# EVB_Gatedriver.net
KiCad netlist of a schematic drawn in Altium Designer
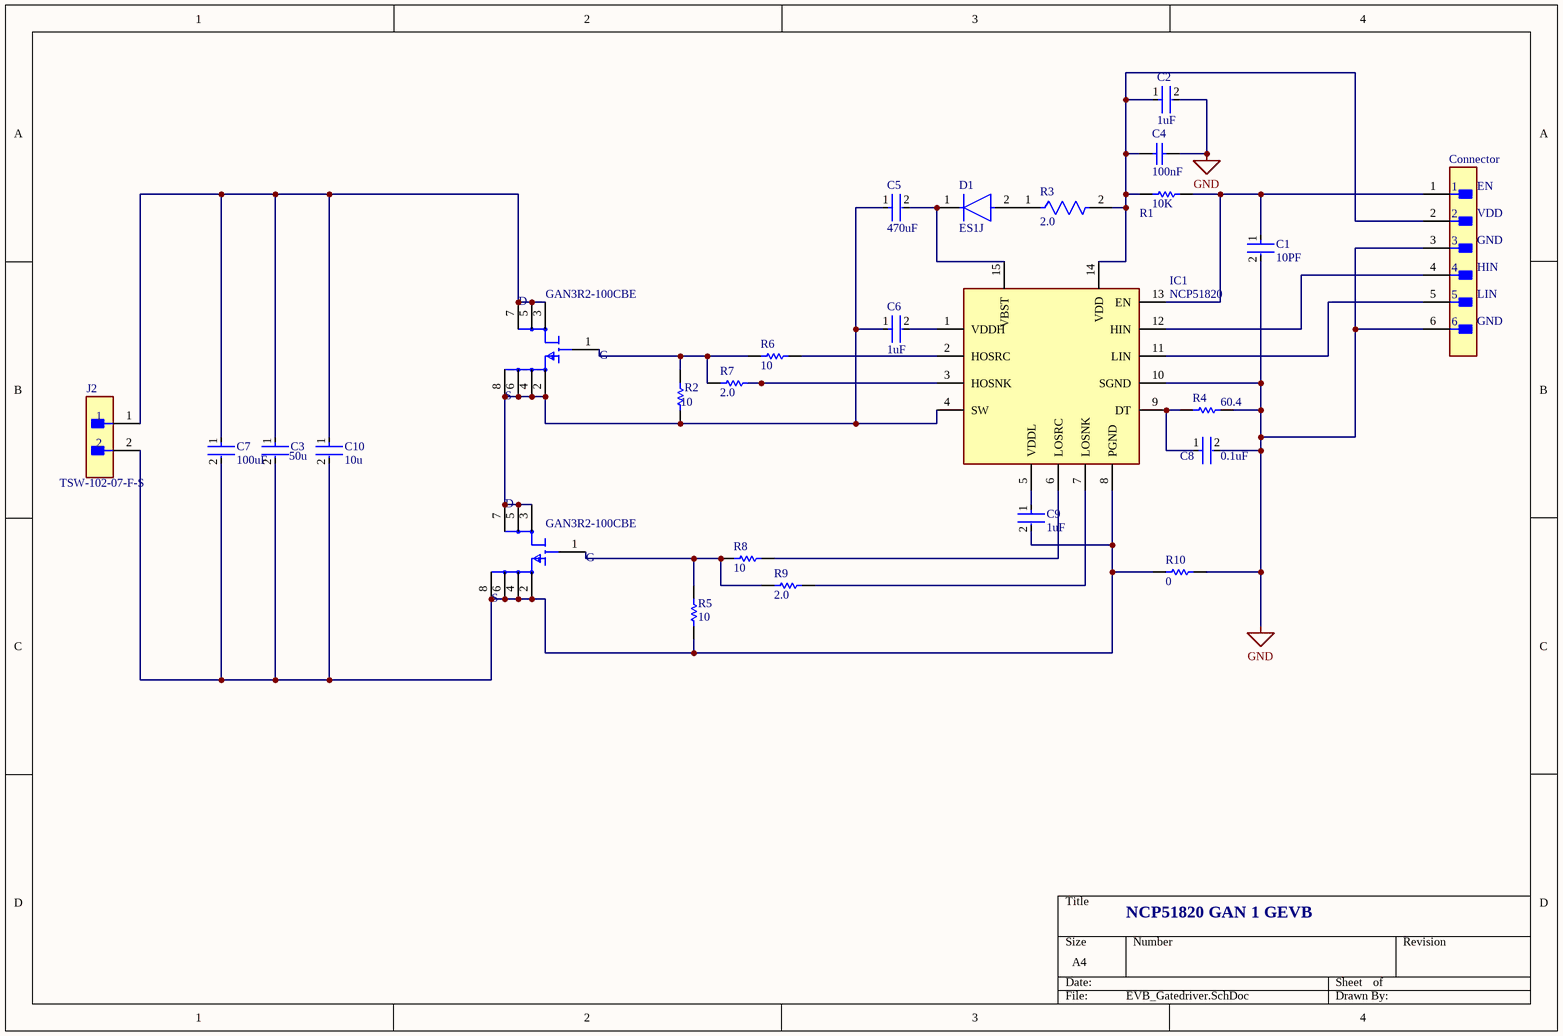
[diagram p0: EVB_Gatedriver.SchDoc]

(export (version "E")
  (design (tool "Eeschema 10.0.6"))
  (components
    (comp (ref "1")
      (value "GAN3R2-100CBE")
      (footprint "FP-WLCSP8-SOT8072-MFG")
      (libsource (lib "Alpha_library") (part "GAN3R2-100CBE_1"))
    )
    (comp (ref "2")
      (value "GAN3R2-100CBE")
      (footprint "FP-WLCSP8-SOT8072-MFG")
      (libsource (lib "Alpha_library") (part "GAN3R2-100CBE_1"))
    )
    (comp (ref "C1")
      (value "10PF")
      (footprint "FP-C1206C-EB-MFG")
      (description "CAP CER 10PF 50V C0G/NP0 1206")
      (fields
        (field (name "OCTOPART") "https://octopart.com/c1206c100j5gactu-kemet-87062")
        (field (name "MANUFACTURER PART NUMBER") "C1206C100J5GACTU")
      )
      (libsource (lib "Altium Content Vault") (part "b4654b650e69147ec39a6b967a45e02"))
    )
    (comp (ref "C2")
      (value "1uF")
      (footprint "FP-CC0805-0_85-MFG")
      (description "CC0805 1 uF X7R 10.00% 16 V")
      (fields (field (name "MANUFACTURER") "Yageo"))
      (libsource (lib "Altium Content Vault") (part "11868f565c42a9108669ba33697ecf6"))
    )
    (comp (ref "C3")
      (value "50u")
      (footprint "FP-CGA5L-0_3-0_1-IPC_B")
      (description "Cap Ceramic 100nF 450V X7T 10% Pad SMD 1206 +125°C Automotive T/R")
      (fields (field (name "TOLERANCE") "10%"))
      (libsource (lib "Altium Content Vault") (part "b4654b650e69147ec39a6b967a45e02"))
    )
    (comp (ref "C4")
      (value "100nF")
      (footprint "CAPC2013X145X48LL20T23")
      (fields (field (name "MANUFACTURER") "Vitramon") (field (name "PART NUMBER") "VJ0805Y104JXXAT"))
      (libsource (lib "Altium Content Vault") (part "CAP"))
    )
    (comp (ref "C5")
      (value "470uF")
      (footprint "FP-C1206C-EB-MFG")
      (description "CAP CER 0.47UF 25V X5R 1206")
      (fields
        (field (name "MANUFACTURER") "KEMET")
        (field (name "OCTOPART") "https://octopart.com/c1206c474k3pactu-kemet-16430430")
      )
      (libsource (lib "Altium Content Vault") (part "b4654b650e69147ec39a6b967a45e02"))
    )
    (comp (ref "C6")
      (value "1uF")
      (footprint "FP-1206-L_3_2_0_15-W_1_6-IPC_A")
      (description "None")
      (fields (field (name "TOLERANCE") "10%") (field (name "VOLTAGE") "25V"))
      (libsource (lib "Altium Content Vault") (part "02cd4be3c70576c341d710602a673aa"))
    )
    (comp (ref "C7")
      (value "100uF")
      (footprint "FP-CGA5L-0_3-0_1-IPC_B")
      (description "Cap Ceramic 100nF 450V X7T 10% Pad SMD 1206 +125°C Automotive T/R")
      (fields (field (name "TOLERANCE") "10%"))
      (libsource (lib "Altium Content Vault") (part "b4654b650e69147ec39a6b967a45e02"))
    )
    (comp (ref "C8")
      (value "0.1uF")
      (footprint "FP-C1206C-EB-MFG")
      (description "CAP CER 0.1UF 25V 10% X7R 1206")
      (fields
        (field (name "MANUFACTURER") "KEMET")
        (field (name "OCTOPART") "https://octopart.com/c1206c104k3ractu-kemet-9144317")
      )
      (libsource (lib "Altium Content Vault") (part "b4654b650e69147ec39a6b967a45e02"))
    )
    (comp (ref "C9")
      (value "1uF")
      (footprint "FP-1206-L_3_2_0_15-W_1_6-IPC_A")
      (description "None")
      (fields (field (name "TOLERANCE") "10%") (field (name "VOLTAGE") "25V"))
      (libsource (lib "Altium Content Vault") (part "02cd4be3c70576c341d710602a673aa"))
    )
    (comp (ref "C10")
      (value "10u")
      (footprint "FP-CGA5L-0_3-0_1-IPC_B")
      (description "Cap Ceramic 100nF 450V X7T 10% Pad SMD 1206 +125°C Automotive T/R")
      (fields (field (name "TOLERANCE") "10%"))
      (libsource (lib "Altium Content Vault") (part "b4654b650e69147ec39a6b967a45e02"))
    )
    (comp (ref "Connector")
      (value "~")
      (footprint "FP-22-28-4060-MFG")
      (description "CONN HEADER VERT 6POS 2.54MM")
      (fields (field (name "MPN") "22-28-4060"))
      (libsource (lib "Altium Content Vault") (part "f2cb566baf1c37ab5a3b8e90bbeafd6"))
    )
    (comp (ref "D1")
      (value "ES1J")
      (footprint "FP-403AE-MFG")
      (description "DIODE GEN PURP 400V 1A SMA")
      (fields
        (field (name "OCTOPART") "https://octopart.com/es1g-on+semiconductor-84324858")
        (field (name "MANUFACTURER") "ON Semiconductor")
      )
      (libsource (lib "Altium Content Vault") (part "d7152d700b627762746794eb795d46e"))
    )
    (comp (ref "IC1")
      (value "NCP51820")
      (footprint "NCP51820")
      (description "Integrated Circuit")
      (libsource (lib "Alpha_library") (part "NCP51820"))
    )
    (comp (ref "J2")
      (value "TSW-102-07-F-S")
      (footprint "FP-TSW-102-07-F-S-MFG")
      (description "CONN HEADER VERT 2POS 2.54MM")
      (libsource (lib "Altium Content Vault") (part "3bc925449376181038e59eaffc5286c"))
    )
    (comp (ref "R1")
      (value "10K")
      (footprint "RESC2013X60X35NL10T20")
      (description "Chip Resistor, 10 KOhm, +/- 1%, 0.125 W, -55 to 155 degC, 0805 (2012 Metric), RoHS, Tape and Reel")
      (fields (field (name "MANUFACTURER") "Yageo"))
      (libsource (lib "Altium Content Vault") (part "RES-2"))
    )
    (comp (ref "R2")
      (value "10")
      (footprint "RESC2013X60X35NL10T20")
      (description "Chip Resistor, 10 KOhm, +/- 1%, 0.125 W, -55 to 155 degC, 0805 (2012 Metric), RoHS, Tape and Reel")
      (fields (field (name "MANUFACTURER") "Yageo"))
      (libsource (lib "Altium Content Vault") (part "RES-2"))
    )
    (comp (ref "R3")
      (value "2.0")
      (footprint "FP-RMCF1206-IPC_C")
      (description "RES 2 OHM 1% 1/4W 1206")
      (fields (field (name "TOLERANCE") "1%"))
      (libsource (lib "Altium Content Vault") (part "1029c3af85768c4190bb7ad29bc67b5"))
    )
    (comp (ref "R4")
      (value "60.4")
      (footprint "RESC3116X65X40LL10T20")
      (fields (field (name "PART NUMBER") "RC1206FR-1360R4L") (field (name "MANUFACTURER") "Yageo"))
      (libsource (lib "Altium Content Vault") (part "RES"))
    )
    (comp (ref "R5")
      (value "10")
      (footprint "RESC2013X60X35NL10T20")
      (description "Chip Resistor, 10 KOhm, +/- 1%, 0.125 W, -55 to 155 degC, 0805 (2012 Metric), RoHS, Tape and Reel")
      (fields (field (name "MANUFACTURER") "Yageo"))
      (libsource (lib "Altium Content Vault") (part "RES-2"))
    )
    (comp (ref "R6")
      (value "10")
      (footprint "RESC2013X60X35ML10T20")
      (description "Chip Resistor, 10 Ohm, +/- 1%, 0.125 W, -55 to 155 degC, 0805 (2012 Metric), RoHS, Tape and Reel")
      (fields (field (name "MANUFACTURER") "Yageo") (field (name "TOLERANCE") "1%"))
      (libsource (lib "Altium Content Vault") (part "RES-2"))
    )
    (comp (ref "R7")
      (value "2.0")
      (footprint "RESC0201(0603)_M")
      (description "2R 0.05W 5% 0201 (0603 Metric)  SMD")
      (fields (field (name "POWER") "0.05 W") (field (name "TOLERANCE") "5 %"))
      (libsource (lib "Altium Content Vault") (part "RES"))
    )
    (comp (ref "R8")
      (value "10")
      (footprint "RESC2013X60X35ML10T20")
      (description "Chip Resistor, 10 Ohm, +/- 1%, 0.125 W, -55 to 155 degC, 0805 (2012 Metric), RoHS, Tape and Reel")
      (fields (field (name "MANUFACTURER") "Yageo") (field (name "TOLERANCE") "1%"))
      (libsource (lib "Altium Content Vault") (part "RES-2"))
    )
    (comp (ref "R9")
      (value "2.0")
      (footprint "RESC0201(0603)_M")
      (description "2R 0.05W 5% 0201 (0603 Metric)  SMD")
      (fields (field (name "POWER") "0.05 W") (field (name "TOLERANCE") "5 %"))
      (libsource (lib "Altium Content Vault") (part "RES"))
    )
    (comp (ref "R10")
      (value "0")
      (footprint "RESC1608X55X25ML10T15")
      (description "Chip Resistor, 0 Ohm, +/- 5%, 0.1 W, -55 to 155 degC, 0603 (1608 Metric), RoHS, Tape and Reel")
      (fields (field (name "TOLERANCE") "5%") (field (name "MANUFACTURER") "Yageo"))
      (libsource (lib "Altium Content Vault") (part "RES-2"))
    )
  )
  (nets
    (net (code "1") (name "GND") (class "Default")
      (node (ref "C1") (pin "2") (pinfunction "2_2") (pintype "passive"))
      (node (ref "C2") (pin "2") (pinfunction "2_2") (pintype "passive"))
      (node (ref "C4") (pin "2") (pinfunction "2_2") (pintype "passive"))
      (node (ref "C8") (pin "2") (pinfunction "2_2") (pintype "passive"))
      (node (ref "Connector") (pin "3") (pinfunction "3_3") (pintype "passive"))
      (node (ref "Connector") (pin "6") (pinfunction "6_6") (pintype "passive"))
      (node (ref "IC1") (pin "10") (pinfunction "SGND_10") (pintype "passive"))
      (node (ref "R10") (pin "2") (pinfunction "2_2") (pintype "passive"))
      (node (ref "R4") (pin "2") (pinfunction "2_2") (pintype "passive"))
    )
    (net (code "2") (name "Net-(1-D-Pad3)") (class "Default")
      (node (ref "1") (pin "3") (pinfunction "D_3") (pintype "passive"))
      (node (ref "1") (pin "5") (pinfunction "D_5") (pintype "passive"))
      (node (ref "1") (pin "7") (pinfunction "D_7") (pintype "passive"))
      (node (ref "C10") (pin "1") (pinfunction "1_1") (pintype "passive"))
      (node (ref "C3") (pin "1") (pinfunction "1_1") (pintype "passive"))
      (node (ref "C7") (pin "1") (pinfunction "1_1") (pintype "passive"))
      (node (ref "J2") (pin "1") (pinfunction "1_1") (pintype "passive"))
    )
    (net (code "3") (name "Net-(1-G)") (class "Default")
      (node (ref "1") (pin "1") (pinfunction "G_1") (pintype "passive"))
      (node (ref "R2") (pin "2") (pinfunction "2_2") (pintype "passive"))
      (node (ref "R6") (pin "1") (pinfunction "1_1") (pintype "passive"))
      (node (ref "R7") (pin "1") (pinfunction "1_1") (pintype "passive"))
    )
    (net (code "4") (name "Net-(2-G)") (class "Default")
      (node (ref "2") (pin "1") (pinfunction "G_1") (pintype "passive"))
      (node (ref "R5") (pin "2") (pinfunction "2_2") (pintype "passive"))
      (node (ref "R8") (pin "1") (pinfunction "1_1") (pintype "passive"))
      (node (ref "R9") (pin "1") (pinfunction "1_1") (pintype "passive"))
    )
    (net (code "5") (name "Net-(D1-A)") (class "Default")
      (node (ref "D1") (pin "2") (pinfunction "A_2") (pintype "passive"))
      (node (ref "R3") (pin "1") (pinfunction "1_1") (pintype "passive"))
    )
    (net (code "6") (name "Net-(D1-C)") (class "Default")
      (node (ref "C5") (pin "2") (pinfunction "2_2") (pintype "passive"))
      (node (ref "D1") (pin "1") (pinfunction "C_1") (pintype "passive"))
      (node (ref "IC1") (pin "15") (pinfunction "VBST_15") (pintype "passive"))
    )
    (net (code "7") (name "Net-(IC1-DT)") (class "Default")
      (node (ref "C8") (pin "1") (pinfunction "1_1") (pintype "passive"))
      (node (ref "IC1") (pin "9") (pinfunction "DT_9") (pintype "passive"))
      (node (ref "R4") (pin "1") (pinfunction "1_1") (pintype "passive"))
    )
    (net (code "8") (name "Net-(IC1-EN)") (class "Default")
      (node (ref "C1") (pin "1") (pinfunction "1_1") (pintype "passive"))
      (node (ref "Connector") (pin "1") (pinfunction "1_1") (pintype "passive"))
      (node (ref "IC1") (pin "13") (pinfunction "EN_13") (pintype "passive"))
      (node (ref "R1") (pin "1") (pinfunction "1_1") (pintype "passive"))
    )
    (net (code "9") (name "Net-(IC1-HIN)") (class "Default")
      (node (ref "Connector") (pin "4") (pinfunction "4_4") (pintype "passive"))
      (node (ref "IC1") (pin "12") (pinfunction "HIN_12") (pintype "passive"))
    )
    (net (code "10") (name "Net-(IC1-HOSNK)") (class "Default")
      (node (ref "IC1") (pin "3") (pinfunction "HOSNK_3") (pintype "passive"))
      (node (ref "R7") (pin "2") (pinfunction "2_2") (pintype "passive"))
    )
    (net (code "11") (name "Net-(IC1-HOSRC)") (class "Default")
      (node (ref "IC1") (pin "2") (pinfunction "HOSRC_2") (pintype "passive"))
      (node (ref "R6") (pin "2") (pinfunction "2_2") (pintype "passive"))
    )
    (net (code "12") (name "Net-(IC1-LIN)") (class "Default")
      (node (ref "Connector") (pin "5") (pinfunction "5_5") (pintype "passive"))
      (node (ref "IC1") (pin "11") (pinfunction "LIN_11") (pintype "passive"))
    )
    (net (code "13") (name "Net-(IC1-LOSNK)") (class "Default")
      (node (ref "IC1") (pin "7") (pinfunction "LOSNK_7") (pintype "passive"))
      (node (ref "R9") (pin "2") (pinfunction "2_2") (pintype "passive"))
    )
    (net (code "14") (name "Net-(IC1-LOSRC)") (class "Default")
      (node (ref "IC1") (pin "6") (pinfunction "LOSRC_6") (pintype "passive"))
      (node (ref "R8") (pin "2") (pinfunction "2_2") (pintype "passive"))
    )
    (net (code "15") (name "Net-(IC1-PGND)") (class "Default")
      (node (ref "2") (pin "2") (pinfunction "S_2") (pintype "passive"))
      (node (ref "2") (pin "4") (pinfunction "S_4") (pintype "passive"))
      (node (ref "2") (pin "6") (pinfunction "S_6") (pintype "passive"))
      (node (ref "2") (pin "8") (pinfunction "S_8") (pintype "passive"))
      (node (ref "C10") (pin "2") (pinfunction "2_2") (pintype "passive"))
      (node (ref "C3") (pin "2") (pinfunction "2_2") (pintype "passive"))
      (node (ref "C7") (pin "2") (pinfunction "2_2") (pintype "passive"))
      (node (ref "C9") (pin "2") (pinfunction "2_2") (pintype "passive"))
      (node (ref "IC1") (pin "8") (pinfunction "PGND_8") (pintype "passive"))
      (node (ref "J2") (pin "2") (pinfunction "2_2") (pintype "passive"))
      (node (ref "R10") (pin "1") (pinfunction "1_1") (pintype "passive"))
      (node (ref "R5") (pin "1") (pinfunction "1_1") (pintype "passive"))
    )
    (net (code "16") (name "Net-(IC1-SW)") (class "Default")
      (node (ref "1") (pin "2") (pinfunction "S_2") (pintype "passive"))
      (node (ref "1") (pin "4") (pinfunction "S_4") (pintype "passive"))
      (node (ref "1") (pin "6") (pinfunction "S_6") (pintype "passive"))
      (node (ref "1") (pin "8") (pinfunction "S_8") (pintype "passive"))
      (node (ref "2") (pin "3") (pinfunction "D_3") (pintype "passive"))
      (node (ref "2") (pin "5") (pinfunction "D_5") (pintype "passive"))
      (node (ref "2") (pin "7") (pinfunction "D_7") (pintype "passive"))
      (node (ref "C5") (pin "1") (pinfunction "1_1") (pintype "passive"))
      (node (ref "C6") (pin "1") (pinfunction "1_1") (pintype "passive"))
      (node (ref "IC1") (pin "4") (pinfunction "SW_4") (pintype "passive"))
      (node (ref "R2") (pin "1") (pinfunction "1_1") (pintype "passive"))
    )
    (net (code "17") (name "Net-(IC1-VDD)") (class "Default")
      (node (ref "C2") (pin "1") (pinfunction "1_1") (pintype "passive"))
      (node (ref "C4") (pin "1") (pinfunction "1_1") (pintype "passive"))
      (node (ref "Connector") (pin "2") (pinfunction "2_2") (pintype "passive"))
      (node (ref "IC1") (pin "14") (pinfunction "VDD_14") (pintype "passive"))
      (node (ref "R1") (pin "2") (pinfunction "2_2") (pintype "passive"))
      (node (ref "R3") (pin "2") (pinfunction "2_2") (pintype "passive"))
    )
    (net (code "18") (name "Net-(IC1-VDDH)") (class "Default")
      (node (ref "C6") (pin "2") (pinfunction "2_2") (pintype "passive"))
      (node (ref "IC1") (pin "1") (pinfunction "VDDH_1") (pintype "passive"))
    )
    (net (code "19") (name "Net-(IC1-VDDL)") (class "Default")
      (node (ref "C9") (pin "1") (pinfunction "1_1") (pintype "passive"))
      (node (ref "IC1") (pin "5") (pinfunction "VDDL_5") (pintype "passive"))
    )
  )
)
